# Socket.net
KiCad netlist of a schematic drawn in Altium Designer
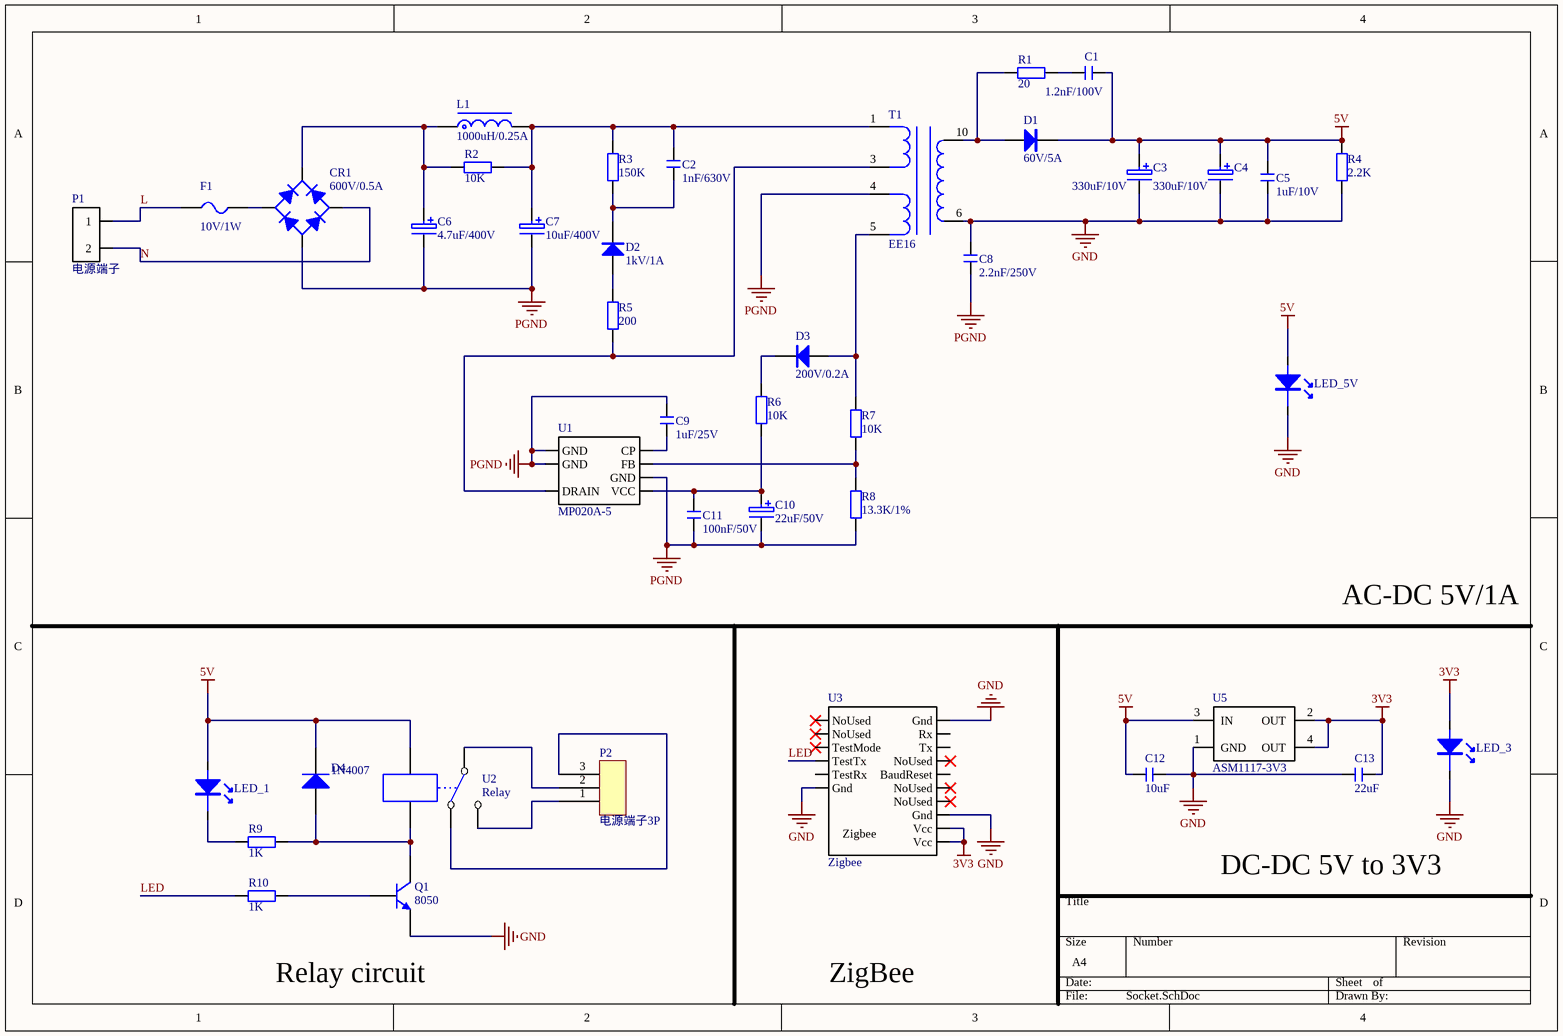
[diagram p0: Socket.SchDoc]

(export (version "E")
  (design (tool "Eeschema 10.0.6"))
  (components
    (comp (ref "C1")
      (value "1.2nF/100V")
      (footprint "C1206")
      (description "无极性贴片电容")
      (fields (field (name "版权归属") "源创客"))
      (libsource (lib "Socket") (part "Cap_C1206"))
    )
    (comp (ref "C2")
      (value "1nF/630V")
      (footprint "C1206")
      (description "无极性贴片电容")
      (fields (field (name "版权归属") "源创客"))
      (libsource (lib "Socket") (part "Cap_C1206"))
    )
    (comp (ref "C3")
      (value "330uF/10V")
      (footprint "C10x16")
      (description "CAP 10*16")
      (fields (field (name "版权归属") "源创客"))
      (libsource (lib "Socket") (part "Cap_E_Middle"))
    )
    (comp (ref "C4")
      (value "330uF/10V")
      (footprint "C10x16")
      (description "CAP 10*16")
      (fields (field (name "版权归属") "源创客"))
      (libsource (lib "Socket") (part "Cap_E_Middle"))
    )
    (comp (ref "C5")
      (value "1uF/10V")
      (footprint "C1206")
      (description "无极性贴片电容")
      (fields (field (name "版权归属") "源创客"))
      (libsource (lib "Socket") (part "Cap_C1206"))
    )
    (comp (ref "C6")
      (value "4.7uF/400V")
      (footprint "C6.3*7")
      (description "CAP 6.3*7")
      (fields (field (name "版权归属") "源创客"))
      (libsource (lib "Socket") (part "Cap_E_Small"))
    )
    (comp (ref "C7")
      (value "10uF/400V")
      (footprint "C6.3*7")
      (description "CAP 6.3*7")
      (fields (field (name "版权归属") "源创客"))
      (libsource (lib "Socket") (part "Cap_E_Small"))
    )
    (comp (ref "C8")
      (value "2.2nF/250V")
      (footprint "C1206")
      (description "无极性贴片电容")
      (fields (field (name "版权归属") "源创客"))
      (libsource (lib "Socket") (part "Cap_C1206"))
    )
    (comp (ref "C9")
      (value "1uF/25V")
      (footprint "C1206")
      (description "无极性贴片电容")
      (fields (field (name "版权归属") "源创客"))
      (libsource (lib "Socket") (part "Cap_C1206"))
    )
    (comp (ref "C10")
      (value "22uF/50V")
      (footprint "C10x16")
      (description "CAP 10*16")
      (fields (field (name "版权归属") "源创客"))
      (libsource (lib "Socket") (part "Cap_E_Middle"))
    )
    (comp (ref "C11")
      (value "100nF/50V")
      (footprint "C1206")
      (description "无极性贴片电容")
      (fields (field (name "版权归属") "源创客"))
      (libsource (lib "Socket") (part "Cap_C1206"))
    )
    (comp (ref "C12")
      (value "10uF")
      (footprint "C1206")
      (description "无极性贴片电容")
      (fields (field (name "版权归属") "源创客"))
      (libsource (lib "Socket") (part "Cap_C1206"))
    )
    (comp (ref "C13")
      (value "22uF")
      (footprint "C1206")
      (description "无极性贴片电容")
      (fields (field (name "版权归属") "源创客"))
      (libsource (lib "Socket") (part "Cap_C1206"))
    )
    (comp (ref "CR1")
      (value "600V/0.5A")
      (footprint "MBS")
      (description "600V/1A整流桥")
      (fields (field (name "版权归属") "源创客"))
      (libsource (lib "Socket") (part "MB6S"))
    )
    (comp (ref "D1")
      (value "60V/5A")
      (footprint "SMC")
      (description "肖特基二极管")
      (fields (field (name "版权归属") "源创客"))
      (libsource (lib "Socket") (part "B560C"))
    )
    (comp (ref "D2")
      (value "1kV/1A")
      (footprint "DO-41")
      (description "快恢复整流二极管")
      (fields (field (name "版权归属") "源创客"))
      (libsource (lib "Socket") (part "FR107"))
    )
    (comp (ref "D3")
      (value "200V/0.2A")
      (footprint "SOD123")
      (description "高速开关二极管")
      (fields (field (name "版权归属") "源创客"))
      (libsource (lib "Socket") (part "BAV21W"))
    )
    (comp (ref "D4")
      (value "1N4007")
      (footprint "DO-41")
      (description "1 Amp General Purpose Rectifier")
      (fields (field (name "PUBLISHER") "Altium Limited"))
      (libsource (lib "Miscellaneous Devices") (part "Diode 1N4007"))
    )
    (comp (ref "F1")
      (value "10V/1W")
      (footprint "FU 1812")
      (description "贴片保险丝_1812")
      (fields (field (name "版权归属") "源创客"))
      (libsource (lib "Socket") (part "FUSE"))
    )
    (comp (ref "L1")
      (value "1000uH/0.25A")
      (footprint "PK0810")
      (description "工字电感")
      (fields (field (name "版权归属") "源创客"))
      (libsource (lib "Socket") (part "L-PK"))
    )
    (comp (ref "LED_1")
      (value "LED_G")
      (footprint "LED1206G")
      (description "1206")
      (libsource (lib "Socket") (part "LED_G"))
    )
    (comp (ref "LED_3")
      (value "LED_G")
      (footprint "LED1206G")
      (description "1206")
      (libsource (lib "Socket") (part "LED_G"))
    )
    (comp (ref "LED_5V")
      (value "LED_G")
      (footprint "LED1206G")
      (description "1206")
      (libsource (lib "Socket") (part "LED_G"))
    )
    (comp (ref "P1")
      (value "电源端子")
      (footprint "KF128-5.08-2P")
      (description "电源端子2P")
      (libsource (lib "Socket") (part "电源端子"))
    )
    (comp (ref "P2") (value "电源端子3P") (footprint "KF128-5.08-3P") (libsource (lib "Socket") (part "电源端子3P")))
    (comp (ref "Q1")
      (value "8050")
      (footprint "SOT-23B_N")
      (description "型号8050 NPN Bipolar Transistor")
      (fields (field (name "PUBLISHER") "Altium Limited"))
      (libsource (lib "Socket") (part "QNPN"))
    )
    (comp (ref "R1")
      (value "20")
      (footprint "R1206")
      (description "1206")
      (libsource (lib "") (part "Res_1"))
    )
    (comp (ref "R2")
      (value "10K")
      (footprint "R1206")
      (description "1206")
      (libsource (lib "") (part "Res_1"))
    )
    (comp (ref "R3")
      (value "150K")
      (footprint "R1206")
      (description "1206")
      (libsource (lib "Socket") (part "Res"))
    )
    (comp (ref "R4")
      (value "2.2K")
      (footprint "R1206")
      (description "1206")
      (libsource (lib "Socket") (part "Res"))
    )
    (comp (ref "R5")
      (value "200")
      (footprint "R1206")
      (description "1206")
      (libsource (lib "Socket") (part "Res"))
    )
    (comp (ref "R6")
      (value "10K")
      (footprint "R1206")
      (description "1206")
      (libsource (lib "Socket") (part "Res"))
    )
    (comp (ref "R7")
      (value "10K")
      (footprint "R1206")
      (description "1206")
      (libsource (lib "Socket") (part "Res"))
    )
    (comp (ref "R8")
      (value "13.3K/1%")
      (footprint "R1206")
      (description "1206")
      (libsource (lib "Socket") (part "Res"))
    )
    (comp (ref "R9")
      (value "1K")
      (footprint "R1206")
      (description "1206")
      (libsource (lib "") (part "Res_2"))
    )
    (comp (ref "R10")
      (value "1K")
      (footprint "R1206")
      (description "1206")
      (libsource (lib "") (part "Res_2"))
    )
    (comp (ref "T1")
      (value "EE16")
      (footprint "EE16")
      (description "高频变压器")
      (fields (field (name "版权归属") "源创客"))
      (libsource (lib "Socket") (part "EE16"))
    )
    (comp (ref "U1")
      (value "MP020A-5")
      (footprint "SOIC8-7A")
      (description "AC-DC")
      (libsource (lib "Socket") (part "MP020A-5"))
    )
    (comp (ref "U2")
      (value "Relay")
      (footprint "SRD-C_Y")
      (description "继电器")
      (libsource (lib "Socket") (part "Relay"))
    )
    (comp (ref "U3")
      (value "Zigbee")
      (footprint "DL-LN_MODE")
      (description "DL-LN33")
      (libsource (lib "Socket") (part "Zigbee"))
    )
    (comp (ref "U5")
      (value "ASM1117-3V3")
      (footprint "SOT-223")
      (description "3V3稳压芯片")
      (libsource (lib "Socket") (part "ASM1117-3V3"))
    )
  )
  (nets
    (net (code "1") (name "/L") (class "Default")
      (node (ref "F1") (pin "1") (pinfunction "1_1") (pintype "passive"))
      (node (ref "P1") (pin "1") (pinfunction "1_1") (pintype "power_in"))
    )
    (net (code "2") (name "/LED") (class "Default")
      (node (ref "R10") (pin "2") (pinfunction "2_2") (pintype "passive"))
      (node (ref "U3") (pin "4") (pinfunction "TestTx_4") (pintype "passive"))
    )
    (net (code "3") (name "/N") (class "Default")
      (node (ref "CR1") (pin "AC1") (pinfunction "AC1_AC1") (pintype "passive"))
      (node (ref "P1") (pin "2") (pinfunction "2_2") (pintype "power_in"))
    )
    (net (code "4") (name "3V3") (class "Default")
      (node (ref "C13") (pin "2") (pinfunction "2_2") (pintype "passive"))
      (node (ref "LED_3") (pin "1") (pinfunction "A_1") (pintype "passive"))
      (node (ref "U3") (pin "7") (pinfunction "Vcc_7") (pintype "passive"))
      (node (ref "U3") (pin "8") (pinfunction "Vcc_8") (pintype "passive"))
      (node (ref "U5") (pin "2") (pinfunction "OUT_2") (pintype "passive"))
      (node (ref "U5") (pin "4") (pinfunction "OUT_4") (pintype "passive"))
    )
    (net (code "5") (name "5V") (class "Default")
      (node (ref "C1") (pin "2") (pinfunction "2_2") (pintype "passive"))
      (node (ref "C12") (pin "1") (pinfunction "1_1") (pintype "passive"))
      (node (ref "C3") (pin "1") (pintype "passive"))
      (node (ref "C4") (pin "1") (pintype "passive"))
      (node (ref "C5") (pin "2") (pinfunction "2_2") (pintype "passive"))
      (node (ref "D1") (pin "2") (pinfunction "K_2") (pintype "passive"))
      (node (ref "D4") (pin "2") (pinfunction "K_2") (pintype "passive"))
      (node (ref "LED_1") (pin "1") (pinfunction "A_1") (pintype "passive"))
      (node (ref "LED_5V") (pin "1") (pinfunction "A_1") (pintype "passive"))
      (node (ref "R4") (pin "2") (pinfunction "2_2") (pintype "passive"))
      (node (ref "U2") (pin "1") (pinfunction "1_1") (pintype "passive"))
      (node (ref "U5") (pin "3") (pinfunction "IN_3") (pintype "passive"))
    )
    (net (code "6") (name "GND") (class "Default")
      (node (ref "C12") (pin "2") (pinfunction "2_2") (pintype "passive"))
      (node (ref "C13") (pin "1") (pinfunction "1_1") (pintype "passive"))
      (node (ref "C3") (pin "2") (pintype "passive"))
      (node (ref "C4") (pin "2") (pintype "passive"))
      (node (ref "C5") (pin "1") (pinfunction "1_1") (pintype "passive"))
      (node (ref "C8") (pin "2") (pinfunction "2_2") (pintype "passive"))
      (node (ref "LED_3") (pin "2") (pinfunction "K_2") (pintype "passive"))
      (node (ref "LED_5V") (pin "2") (pinfunction "K_2") (pintype "passive"))
      (node (ref "Q1") (pin "3") (pinfunction "E_3") (pintype "passive"))
      (node (ref "R4") (pin "1") (pinfunction "1_1") (pintype "passive"))
      (node (ref "T1") (pin "6") (pinfunction "6_6") (pintype "passive"))
      (node (ref "U3") (pin "16") (pinfunction "Gnd_16") (pintype "passive"))
      (node (ref "U3") (pin "6") (pinfunction "Gnd_6") (pintype "passive"))
      (node (ref "U3") (pin "9") (pinfunction "Gnd_9") (pintype "passive"))
      (node (ref "U5") (pin "1") (pinfunction "GND_1") (pintype "passive"))
    )
    (net (code "7") (name "Net-(C1-Pad1)") (class "Default")
      (node (ref "C1") (pin "1") (pinfunction "1_1") (pintype "passive"))
      (node (ref "R1") (pin "2") (pinfunction "2_2") (pintype "passive"))
    )
    (net (code "8") (name "Net-(C2-Pad2)") (class "Default")
      (node (ref "C2") (pin "2") (pinfunction "2_2") (pintype "passive"))
      (node (ref "C7") (pin "1") (pintype "passive"))
      (node (ref "L1") (pin "2") (pinfunction "2_2") (pintype "passive"))
      (node (ref "R2") (pin "2") (pinfunction "2_2") (pintype "passive"))
      (node (ref "R3") (pin "2") (pinfunction "2_2") (pintype "passive"))
      (node (ref "T1") (pin "1") (pinfunction "1_1") (pintype "passive"))
    )
    (net (code "9") (name "Net-(C6-Pad1)") (class "Default")
      (node (ref "C6") (pin "1") (pintype "passive"))
      (node (ref "CR1") (pin "DC+") (pinfunction "DC+_DC+") (pintype "passive"))
      (node (ref "L1") (pin "1") (pinfunction "1_1") (pintype "passive"))
      (node (ref "R2") (pin "1") (pinfunction "1_1") (pintype "passive"))
    )
    (net (code "10") (name "Net-(CR1-PadAC2)") (class "Default")
      (node (ref "CR1") (pin "AC2") (pinfunction "AC2_AC2") (pintype "passive"))
      (node (ref "F1") (pin "2") (pinfunction "2_2") (pintype "passive"))
    )
    (net (code "11") (name "Net-(D1-A)") (class "Default")
      (node (ref "D1") (pin "1") (pinfunction "A_1") (pintype "passive"))
      (node (ref "R1") (pin "1") (pinfunction "1_1") (pintype "passive"))
      (node (ref "T1") (pin "10") (pinfunction "10_10") (pintype "passive"))
    )
    (net (code "12") (name "Net-(D2-A)") (class "Default")
      (node (ref "D2") (pin "1") (pinfunction "A_1") (pintype "passive"))
      (node (ref "R5") (pin "2") (pinfunction "2_2") (pintype "passive"))
    )
    (net (code "13") (name "Net-(D2-K)") (class "Default")
      (node (ref "C2") (pin "1") (pinfunction "1_1") (pintype "passive"))
      (node (ref "D2") (pin "2") (pinfunction "K_2") (pintype "passive"))
      (node (ref "R3") (pin "1") (pinfunction "1_1") (pintype "passive"))
    )
    (net (code "14") (name "Net-(D3-A)") (class "Default")
      (node (ref "D3") (pin "1") (pinfunction "A_1") (pintype "passive"))
      (node (ref "R7") (pin "2") (pinfunction "2_2") (pintype "passive"))
      (node (ref "T1") (pin "5") (pinfunction "5_5") (pintype "passive"))
    )
    (net (code "15") (name "Net-(D3-K)") (class "Default")
      (node (ref "D3") (pin "2") (pinfunction "K_2") (pintype "passive"))
      (node (ref "R6") (pin "2") (pinfunction "2_2") (pintype "passive"))
    )
    (net (code "16") (name "Net-(D4-A)") (class "Default")
      (node (ref "D4") (pin "1") (pinfunction "A_1") (pintype "passive"))
      (node (ref "Q1") (pin "1") (pinfunction "C_1") (pintype "passive"))
      (node (ref "R9") (pin "1") (pinfunction "1_1") (pintype "passive"))
      (node (ref "U2") (pin "2") (pinfunction "2_2") (pintype "passive"))
    )
    (net (code "17") (name "Net-(LED_1-K)") (class "Default")
      (node (ref "LED_1") (pin "2") (pinfunction "K_2") (pintype "passive"))
      (node (ref "R9") (pin "2") (pinfunction "2_2") (pintype "passive"))
    )
    (net (code "18") (name "Net-(P2-Pad1)") (class "Default")
      (node (ref "P2") (pin "1") (pinfunction "1_1") (pintype "passive"))
      (node (ref "U2") (pin "5") (pinfunction "5_5") (pintype "passive"))
    )
    (net (code "19") (name "Net-(P2-Pad2)") (class "Default")
      (node (ref "P2") (pin "2") (pinfunction "2_2") (pintype "passive"))
      (node (ref "U2") (pin "3") (pinfunction "3_3") (pintype "passive"))
    )
    (net (code "20") (name "Net-(P2-Pad3)") (class "Default")
      (node (ref "P2") (pin "3") (pinfunction "3_3") (pintype "passive"))
      (node (ref "U2") (pin "4") (pinfunction "4_4") (pintype "passive"))
    )
    (net (code "21") (name "Net-(Q1-B)") (class "Default")
      (node (ref "Q1") (pin "2") (pinfunction "B_2") (pintype "passive"))
      (node (ref "R10") (pin "1") (pinfunction "1_1") (pintype "passive"))
    )
    (net (code "22") (name "Net-(U1-CP)") (class "Default")
      (node (ref "C9") (pin "1") (pinfunction "1_1") (pintype "passive"))
      (node (ref "U1") (pin "4") (pinfunction "CP_4") (pintype "passive"))
    )
    (net (code "23") (name "Net-(U1-DRAIN)") (class "Default")
      (node (ref "R5") (pin "1") (pinfunction "1_1") (pintype "passive"))
      (node (ref "T1") (pin "3") (pinfunction "3_3") (pintype "passive"))
      (node (ref "U1") (pin "8") (pinfunction "DRAIN_8") (pintype "passive"))
    )
    (net (code "24") (name "Net-(U1-FB)") (class "Default")
      (node (ref "R7") (pin "1") (pinfunction "1_1") (pintype "passive"))
      (node (ref "R8") (pin "2") (pinfunction "2_2") (pintype "passive"))
      (node (ref "U1") (pin "3") (pinfunction "FB_3") (pintype "passive"))
    )
    (net (code "25") (name "Net-(U1-VCC)") (class "Default")
      (node (ref "C10") (pin "1") (pintype "passive"))
      (node (ref "C11") (pin "2") (pinfunction "2_2") (pintype "passive"))
      (node (ref "R6") (pin "1") (pinfunction "1_1") (pintype "passive"))
      (node (ref "U1") (pin "1") (pinfunction "VCC_1") (pintype "passive"))
    )
    (net (code "26") (name "PGND") (class "Default")
      (node (ref "C10") (pin "2") (pintype "passive"))
      (node (ref "C11") (pin "1") (pinfunction "1_1") (pintype "passive"))
      (node (ref "C6") (pin "2") (pintype "passive"))
      (node (ref "C7") (pin "2") (pintype "passive"))
      (node (ref "C8") (pin "1") (pinfunction "1_1") (pintype "passive"))
      (node (ref "C9") (pin "2") (pinfunction "2_2") (pintype "passive"))
      (node (ref "CR1") (pin "DC-") (pinfunction "DC-_DC-") (pintype "passive"))
      (node (ref "R8") (pin "1") (pinfunction "1_1") (pintype "passive"))
      (node (ref "T1") (pin "4") (pinfunction "4_4") (pintype "passive"))
      (node (ref "U1") (pin "2") (pinfunction "GND_2") (pintype "passive"))
      (node (ref "U1") (pin "5") (pinfunction "GND_5") (pintype "passive"))
      (node (ref "U1") (pin "6") (pinfunction "GND_6") (pintype "passive"))
    )
    (net (code "27") (name "unconnected-(U3-BaudReset-Pad12)") (class "Default")
      (node (ref "U3") (pin "12") (pinfunction "BaudReset_12") (pintype "passive"))
    )
    (net (code "28") (name "unconnected-(U3-NoUsed-Pad1)") (class "Default")
      (node (ref "U3") (pin "1") (pinfunction "NoUsed_1") (pintype "passive+no_connect"))
    )
    (net (code "29") (name "unconnected-(U3-NoUsed-Pad2)") (class "Default")
      (node (ref "U3") (pin "2") (pinfunction "NoUsed_2") (pintype "passive+no_connect"))
    )
    (net (code "30") (name "unconnected-(U3-NoUsed-Pad10)") (class "Default")
      (node (ref "U3") (pin "10") (pinfunction "NoUsed_10") (pintype "passive+no_connect"))
    )
    (net (code "31") (name "unconnected-(U3-NoUsed-Pad11)") (class "Default")
      (node (ref "U3") (pin "11") (pinfunction "NoUsed_11") (pintype "passive+no_connect"))
    )
    (net (code "32") (name "unconnected-(U3-NoUsed-Pad13)") (class "Default")
      (node (ref "U3") (pin "13") (pinfunction "NoUsed_13") (pintype "passive+no_connect"))
    )
    (net (code "33") (name "unconnected-(U3-Rx-Pad15)") (class "Default")
      (node (ref "U3") (pin "15") (pinfunction "Rx_15") (pintype "passive"))
    )
    (net (code "34") (name "unconnected-(U3-TestMode-Pad3)") (class "Default")
      (node (ref "U3") (pin "3") (pinfunction "TestMode_3") (pintype "passive+no_connect"))
    )
    (net (code "35") (name "unconnected-(U3-TestRx-Pad5)") (class "Default")
      (node (ref "U3") (pin "5") (pinfunction "TestRx_5") (pintype "passive"))
    )
    (net (code "36") (name "unconnected-(U3-Tx-Pad14)") (class "Default")
      (node (ref "U3") (pin "14") (pinfunction "Tx_14") (pintype "passive"))
    )
  )
)
